# Netzteil_CA1_Frontpanel.net
KiCad netlist of a schematic drawn in EAGLE
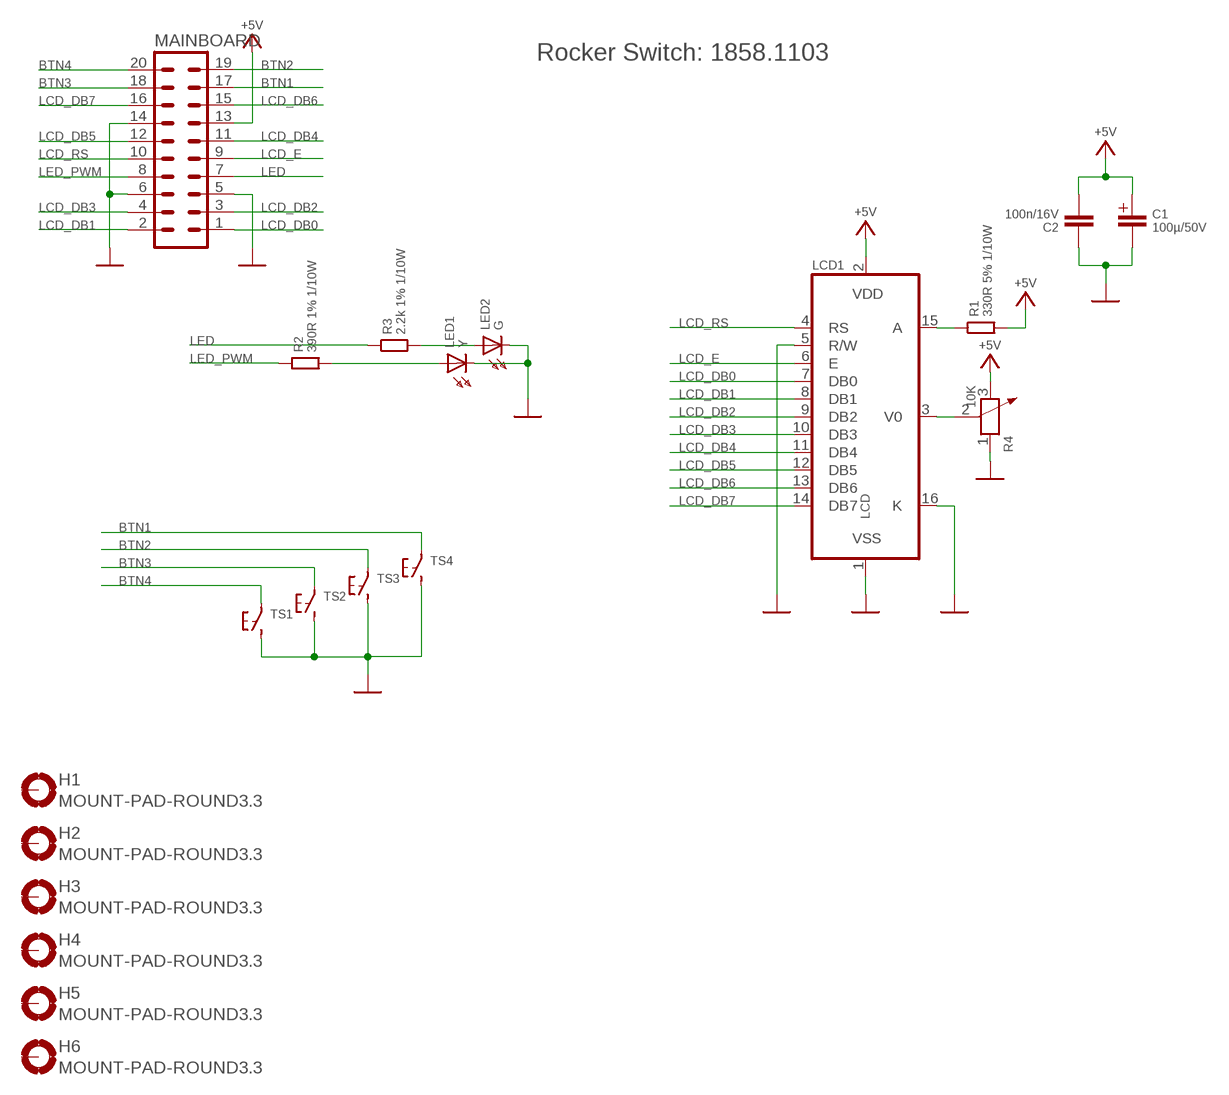
[diagram p0: schematic, sheet 1]

(export (version "E")
  (design (tool "Eeschema 10.0.6"))
  (components
    (comp (ref "C1")
      (value "100µ/50V")
      (footprint "eagle-import:C+_3.5_8")
      (libsource (lib "eagle-import") (part "C+3.5/8"))
    )
    (comp (ref "C2")
      (value "100n/16V")
      (footprint "eagle-import:0805")
      (libsource (lib "eagle-import") (part "CC/0805"))
    )
    (comp (ref "H1")
      (value "MOUNT-PAD-ROUND3.3")
      (footprint "eagle-import:3,3-PAD")
      (libsource (lib "eagle-import") (part "MOUNT-PAD-ROUND3.3"))
    )
    (comp (ref "H2")
      (value "MOUNT-PAD-ROUND3.3")
      (footprint "eagle-import:3,3-PAD")
      (libsource (lib "eagle-import") (part "MOUNT-PAD-ROUND3.3"))
    )
    (comp (ref "H3")
      (value "MOUNT-PAD-ROUND3.3")
      (footprint "eagle-import:3,3-PAD")
      (libsource (lib "eagle-import") (part "MOUNT-PAD-ROUND3.3"))
    )
    (comp (ref "H4")
      (value "MOUNT-PAD-ROUND3.3")
      (footprint "eagle-import:3,3-PAD")
      (libsource (lib "eagle-import") (part "MOUNT-PAD-ROUND3.3"))
    )
    (comp (ref "H5")
      (value "MOUNT-PAD-ROUND3.3")
      (footprint "eagle-import:3,3-PAD")
      (libsource (lib "eagle-import") (part "MOUNT-PAD-ROUND3.3"))
    )
    (comp (ref "H6")
      (value "MOUNT-PAD-ROUND3.3")
      (footprint "eagle-import:3,3-PAD")
      (libsource (lib "eagle-import") (part "MOUNT-PAD-ROUND3.3"))
    )
    (comp (ref "LCD1")
      (value "LCD")
      (footprint "eagle-import:DISPLAYTECH-204C")
      (libsource (lib "eagle-import") (part "LCD"))
    )
    (comp (ref "LED1")
      (value "Y")
      (footprint "eagle-import:LED0805")
      (libsource (lib "eagle-import") (part "LED0805"))
    )
    (comp (ref "LED2")
      (value "G")
      (footprint "eagle-import:LED0805")
      (libsource (lib "eagle-import") (part "LED0805"))
    )
    (comp (ref "MAINBOARD")
      (value "MA10-2")
      (footprint "eagle-import:MA10-2")
      (libsource (lib "eagle-import") (part "MA10-2"))
    )
    (comp (ref "R1")
      (value "330R 5% 1/10W")
      (footprint "eagle-import:C0805K")
      (libsource (lib "eagle-import") (part "R-SMD0805"))
    )
    (comp (ref "R2")
      (value "390R 1% 1/10W")
      (footprint "eagle-import:C0805K")
      (libsource (lib "eagle-import") (part "R-SMD0805"))
    )
    (comp (ref "R3")
      (value "2.2k 1% 1/10W")
      (footprint "eagle-import:C0805K")
      (libsource (lib "eagle-import") (part "R-SMD0805"))
    )
    (comp (ref "R4")
      (value "10K")
      (footprint "eagle-import:ADJR3-7.0X7.0X5.0MM")
      (fields (field (name "MPN") "SX3362P"))
      (libsource (lib "eagle-import") (part "TRIMPOT"))
    )
    (comp (ref "TS1")
      (value "TS1B3F-10XX")
      (footprint "eagle-import:B3F-10XX")
      (libsource (lib "eagle-import") (part "TS1B3F-10XX"))
    )
    (comp (ref "TS2")
      (value "TS1B3F-10XX")
      (footprint "eagle-import:B3F-10XX")
      (libsource (lib "eagle-import") (part "TS1B3F-10XX"))
    )
    (comp (ref "TS3")
      (value "TS1B3F-10XX")
      (footprint "eagle-import:B3F-10XX")
      (libsource (lib "eagle-import") (part "TS1B3F-10XX"))
    )
    (comp (ref "TS4")
      (value "TS1B3F-10XX")
      (footprint "eagle-import:B3F-10XX")
      (libsource (lib "eagle-import") (part "TS1B3F-10XX"))
    )
  )
  (nets
    (net (code "1") (name "+5V") (class "Default")
      (node (ref "C1") (pin "+") (pinfunction "+_+") (pintype "passive"))
      (node (ref "C2") (pin "2") (pinfunction "2_2") (pintype "passive"))
      (node (ref "LCD1") (pin "2") (pinfunction "VDD_2") (pintype "power_in"))
      (node (ref "MAINBOARD") (pin "13") (pinfunction "13_13") (pintype "passive"))
      (node (ref "R1") (pin "2") (pinfunction "2_2") (pintype "passive"))
      (node (ref "R4") (pin "3") (pinfunction "3_3") (pintype "passive"))
    )
    (net (code "2") (name "/BTN1") (class "Default")
      (node (ref "MAINBOARD") (pin "17") (pinfunction "17_17") (pintype "passive"))
      (node (ref "TS4") (pin "1") (pinfunction "1_1") (pintype "passive"))
    )
    (net (code "3") (name "/BTN2") (class "Default")
      (node (ref "MAINBOARD") (pin "19") (pinfunction "19_19") (pintype "passive"))
      (node (ref "TS3") (pin "1") (pinfunction "1_1") (pintype "passive"))
    )
    (net (code "4") (name "/BTN3") (class "Default")
      (node (ref "MAINBOARD") (pin "18") (pinfunction "18_18") (pintype "passive"))
      (node (ref "TS2") (pin "1") (pinfunction "1_1") (pintype "passive"))
    )
    (net (code "5") (name "/BTN4") (class "Default")
      (node (ref "MAINBOARD") (pin "20") (pinfunction "20_20") (pintype "passive"))
      (node (ref "TS1") (pin "1") (pinfunction "1_1") (pintype "passive"))
    )
    (net (code "6") (name "/LCD_DB0") (class "Default")
      (node (ref "LCD1") (pin "7") (pinfunction "DB0_7") (pintype "passive"))
      (node (ref "MAINBOARD") (pin "1") (pinfunction "1_1") (pintype "passive"))
    )
    (net (code "7") (name "/LCD_DB1") (class "Default")
      (node (ref "LCD1") (pin "8") (pinfunction "DB1_8") (pintype "passive"))
      (node (ref "MAINBOARD") (pin "2") (pinfunction "2_2") (pintype "passive"))
    )
    (net (code "8") (name "/LCD_DB2") (class "Default")
      (node (ref "LCD1") (pin "9") (pinfunction "DB2_9") (pintype "passive"))
      (node (ref "MAINBOARD") (pin "3") (pinfunction "3_3") (pintype "passive"))
    )
    (net (code "9") (name "/LCD_DB3") (class "Default")
      (node (ref "LCD1") (pin "10") (pinfunction "DB3_10") (pintype "passive"))
      (node (ref "MAINBOARD") (pin "4") (pinfunction "4_4") (pintype "passive"))
    )
    (net (code "10") (name "/LCD_DB4") (class "Default")
      (node (ref "LCD1") (pin "11") (pinfunction "DB4_11") (pintype "passive"))
      (node (ref "MAINBOARD") (pin "11") (pinfunction "11_11") (pintype "passive"))
    )
    (net (code "11") (name "/LCD_DB5") (class "Default")
      (node (ref "LCD1") (pin "12") (pinfunction "DB5_12") (pintype "passive"))
      (node (ref "MAINBOARD") (pin "12") (pinfunction "12_12") (pintype "passive"))
    )
    (net (code "12") (name "/LCD_DB6") (class "Default")
      (node (ref "LCD1") (pin "13") (pinfunction "DB6_13") (pintype "passive"))
      (node (ref "MAINBOARD") (pin "15") (pinfunction "15_15") (pintype "passive"))
    )
    (net (code "13") (name "/LCD_DB7") (class "Default")
      (node (ref "LCD1") (pin "14") (pinfunction "DB7_14") (pintype "passive"))
      (node (ref "MAINBOARD") (pin "16") (pinfunction "16_16") (pintype "passive"))
    )
    (net (code "14") (name "/LCD_E") (class "Default")
      (node (ref "LCD1") (pin "6") (pinfunction "E_6") (pintype "passive"))
      (node (ref "MAINBOARD") (pin "9") (pinfunction "9_9") (pintype "passive"))
    )
    (net (code "15") (name "/LCD_RS") (class "Default")
      (node (ref "LCD1") (pin "4") (pinfunction "RS_4") (pintype "passive"))
      (node (ref "MAINBOARD") (pin "10") (pinfunction "10_10") (pintype "passive"))
    )
    (net (code "16") (name "/LED") (class "Default")
      (node (ref "MAINBOARD") (pin "7") (pinfunction "7_7") (pintype "passive"))
      (node (ref "R3") (pin "1") (pinfunction "1_1") (pintype "passive"))
    )
    (net (code "17") (name "/LED_PWM") (class "Default")
      (node (ref "MAINBOARD") (pin "8") (pinfunction "8_8") (pintype "passive"))
      (node (ref "R2") (pin "1") (pinfunction "1_1") (pintype "passive"))
    )
    (net (code "18") (name "Net-(LCD1-A)") (class "Default")
      (node (ref "LCD1") (pin "15") (pinfunction "A_15") (pintype "passive"))
      (node (ref "R1") (pin "1") (pinfunction "1_1") (pintype "passive"))
    )
    (net (code "19") (name "Net-(LCD1-V0)") (class "Default")
      (node (ref "LCD1") (pin "3") (pinfunction "V0_3") (pintype "passive"))
      (node (ref "R4") (pin "2") (pinfunction "2_2") (pintype "passive"))
    )
    (net (code "20") (name "Net-(LED1-PadA)") (class "Default")
      (node (ref "LED1") (pin "A") (pinfunction "A_A") (pintype "passive"))
      (node (ref "R2") (pin "2") (pinfunction "2_2") (pintype "passive"))
    )
    (net (code "21") (name "Net-(LED2-PadA)") (class "Default")
      (node (ref "LED2") (pin "A") (pinfunction "A_A") (pintype "passive"))
      (node (ref "R3") (pin "2") (pinfunction "2_2") (pintype "passive"))
    )
    (net (code "22") (name "VSS") (class "Default")
      (node (ref "C1") (pin "-") (pinfunction "-_-") (pintype "passive"))
      (node (ref "C2") (pin "1") (pinfunction "1_1") (pintype "passive"))
      (node (ref "LCD1") (pin "1") (pinfunction "VSS_1") (pintype "power_in"))
      (node (ref "LCD1") (pin "16") (pinfunction "K_16") (pintype "passive"))
      (node (ref "LCD1") (pin "5") (pinfunction "R/W_5") (pintype "passive"))
      (node (ref "LED1") (pin "C") (pinfunction "C_C") (pintype "passive"))
      (node (ref "LED2") (pin "C") (pinfunction "C_C") (pintype "passive"))
      (node (ref "MAINBOARD") (pin "14") (pinfunction "14_14") (pintype "passive"))
      (node (ref "MAINBOARD") (pin "5") (pinfunction "5_5") (pintype "passive"))
      (node (ref "MAINBOARD") (pin "6") (pinfunction "6_6") (pintype "passive"))
      (node (ref "R4") (pin "1") (pinfunction "1_1") (pintype "passive"))
      (node (ref "TS1") (pin "3") (pinfunction "2_3") (pintype "passive"))
      (node (ref "TS2") (pin "3") (pinfunction "2_3") (pintype "passive"))
      (node (ref "TS3") (pin "3") (pinfunction "2_3") (pintype "passive"))
      (node (ref "TS4") (pin "3") (pinfunction "2_3") (pintype "passive"))
    )
    (net (code "23") (name "unconnected-(H1-MOUNT-PadB3,3)") (class "Default")
      (node (ref "H1") (pin "B3,3") (pinfunction "MOUNT_B3,3") (pintype "passive"))
    )
    (net (code "24") (name "unconnected-(H2-MOUNT-PadB3,3)") (class "Default")
      (node (ref "H2") (pin "B3,3") (pinfunction "MOUNT_B3,3") (pintype "passive"))
    )
    (net (code "25") (name "unconnected-(H3-MOUNT-PadB3,3)") (class "Default")
      (node (ref "H3") (pin "B3,3") (pinfunction "MOUNT_B3,3") (pintype "passive"))
    )
    (net (code "26") (name "unconnected-(H4-MOUNT-PadB3,3)") (class "Default")
      (node (ref "H4") (pin "B3,3") (pinfunction "MOUNT_B3,3") (pintype "passive"))
    )
    (net (code "27") (name "unconnected-(H5-MOUNT-PadB3,3)") (class "Default")
      (node (ref "H5") (pin "B3,3") (pinfunction "MOUNT_B3,3") (pintype "passive"))
    )
    (net (code "28") (name "unconnected-(H6-MOUNT-PadB3,3)") (class "Default")
      (node (ref "H6") (pin "B3,3") (pinfunction "MOUNT_B3,3") (pintype "passive"))
    )
  )
)
